# SiPM_Ada_S13360_v05_DualTip.net
KiCad netlist of a schematic drawn in EAGLE
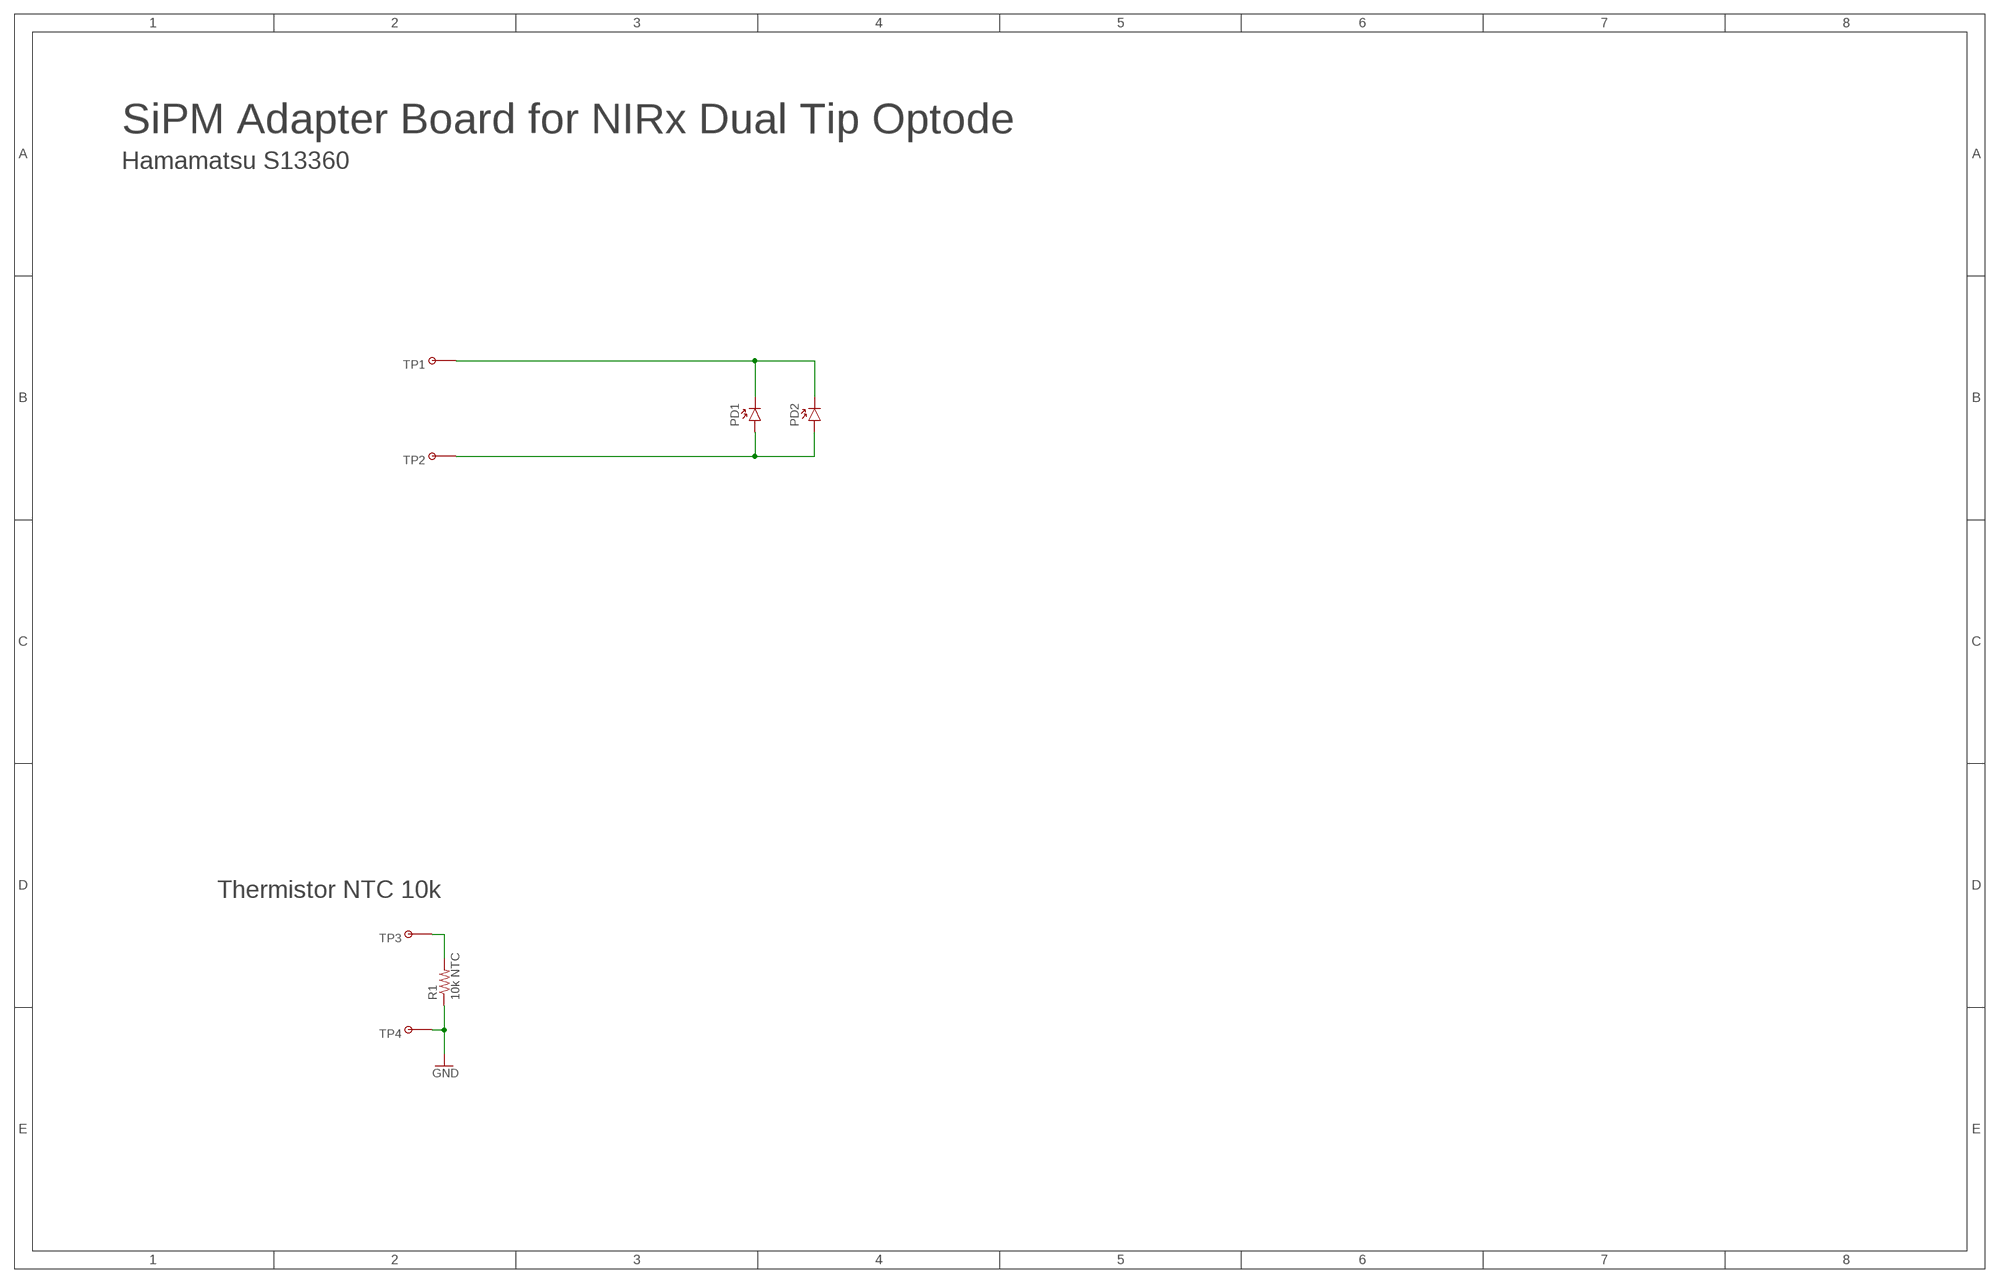
[diagram p0: schematic, sheet 1]

(export (version "E")
  (design (tool "Eeschema 10.0.6"))
  (components
    (comp (ref "PD1")
      (value "PHOTODIODE_S13360-30XXPE")
      (footprint "eagle-import:S13360-30XXPE")
      (libsource (lib "eagle-import") (part "PHOTODIODE_S13360-30XXPE"))
    )
    (comp (ref "PD2")
      (value "PHOTODIODE_S13360-30XXPE")
      (footprint "eagle-import:S13360-30XXPE")
      (libsource (lib "eagle-import") (part "PHOTODIODE_S13360-30XXPE"))
    )
    (comp (ref "R1")
      (value "10k NTC")
      (footprint "eagle-import:0603-RES")
      (libsource (lib "eagle-import") (part "RESISTOR0603-RES"))
    )
    (comp (ref "TP1")
      (value "TESTPOINT_PADMEDIUM")
      (footprint "eagle-import:TESTPAD_MEDIUM")
      (libsource (lib "eagle-import") (part "TESTPOINT_PADMEDIUM"))
    )
    (comp (ref "TP2")
      (value "TESTPOINT_PADMEDIUM")
      (footprint "eagle-import:TESTPAD_MEDIUM")
      (libsource (lib "eagle-import") (part "TESTPOINT_PADMEDIUM"))
    )
    (comp (ref "TP3")
      (value "TESTPOINT_PADMEDIUM")
      (footprint "eagle-import:TESTPAD_MEDIUM")
      (libsource (lib "eagle-import") (part "TESTPOINT_PADMEDIUM"))
    )
    (comp (ref "TP4")
      (value "TESTPOINT_PADMEDIUM")
      (footprint "eagle-import:TESTPAD_MEDIUM")
      (libsource (lib "eagle-import") (part "TESTPOINT_PADMEDIUM"))
    )
  )
  (nets
    (net (code "1") (name "GND") (class "Default")
      (node (ref "R1") (pin "1") (pinfunction "1_1") (pintype "passive"))
      (node (ref "TP4") (pin "P$1") (pinfunction "P$1_P$1") (pintype "bidirectional"))
    )
    (net (code "2") (name "Net-(PD1-PadA)") (class "Default")
      (node (ref "PD1") (pin "A") (pinfunction "A_A") (pintype "bidirectional"))
      (node (ref "PD2") (pin "A") (pinfunction "A_A") (pintype "bidirectional"))
      (node (ref "TP2") (pin "P$1") (pinfunction "P$1_P$1") (pintype "bidirectional"))
    )
    (net (code "3") (name "Net-(PD1-PadC)") (class "Default")
      (node (ref "PD1") (pin "C") (pinfunction "C_C") (pintype "bidirectional"))
      (node (ref "PD2") (pin "C") (pinfunction "C_C") (pintype "bidirectional"))
      (node (ref "TP1") (pin "P$1") (pinfunction "P$1_P$1") (pintype "bidirectional"))
    )
    (net (code "4") (name "Net-(R1-Pad2)") (class "Default")
      (node (ref "R1") (pin "2") (pinfunction "2_2") (pintype "passive"))
      (node (ref "TP3") (pin "P$1") (pinfunction "P$1_P$1") (pintype "bidirectional"))
    )
  )
)
